# MCU.net
KiCad netlist of a schematic drawn in Altium Designer
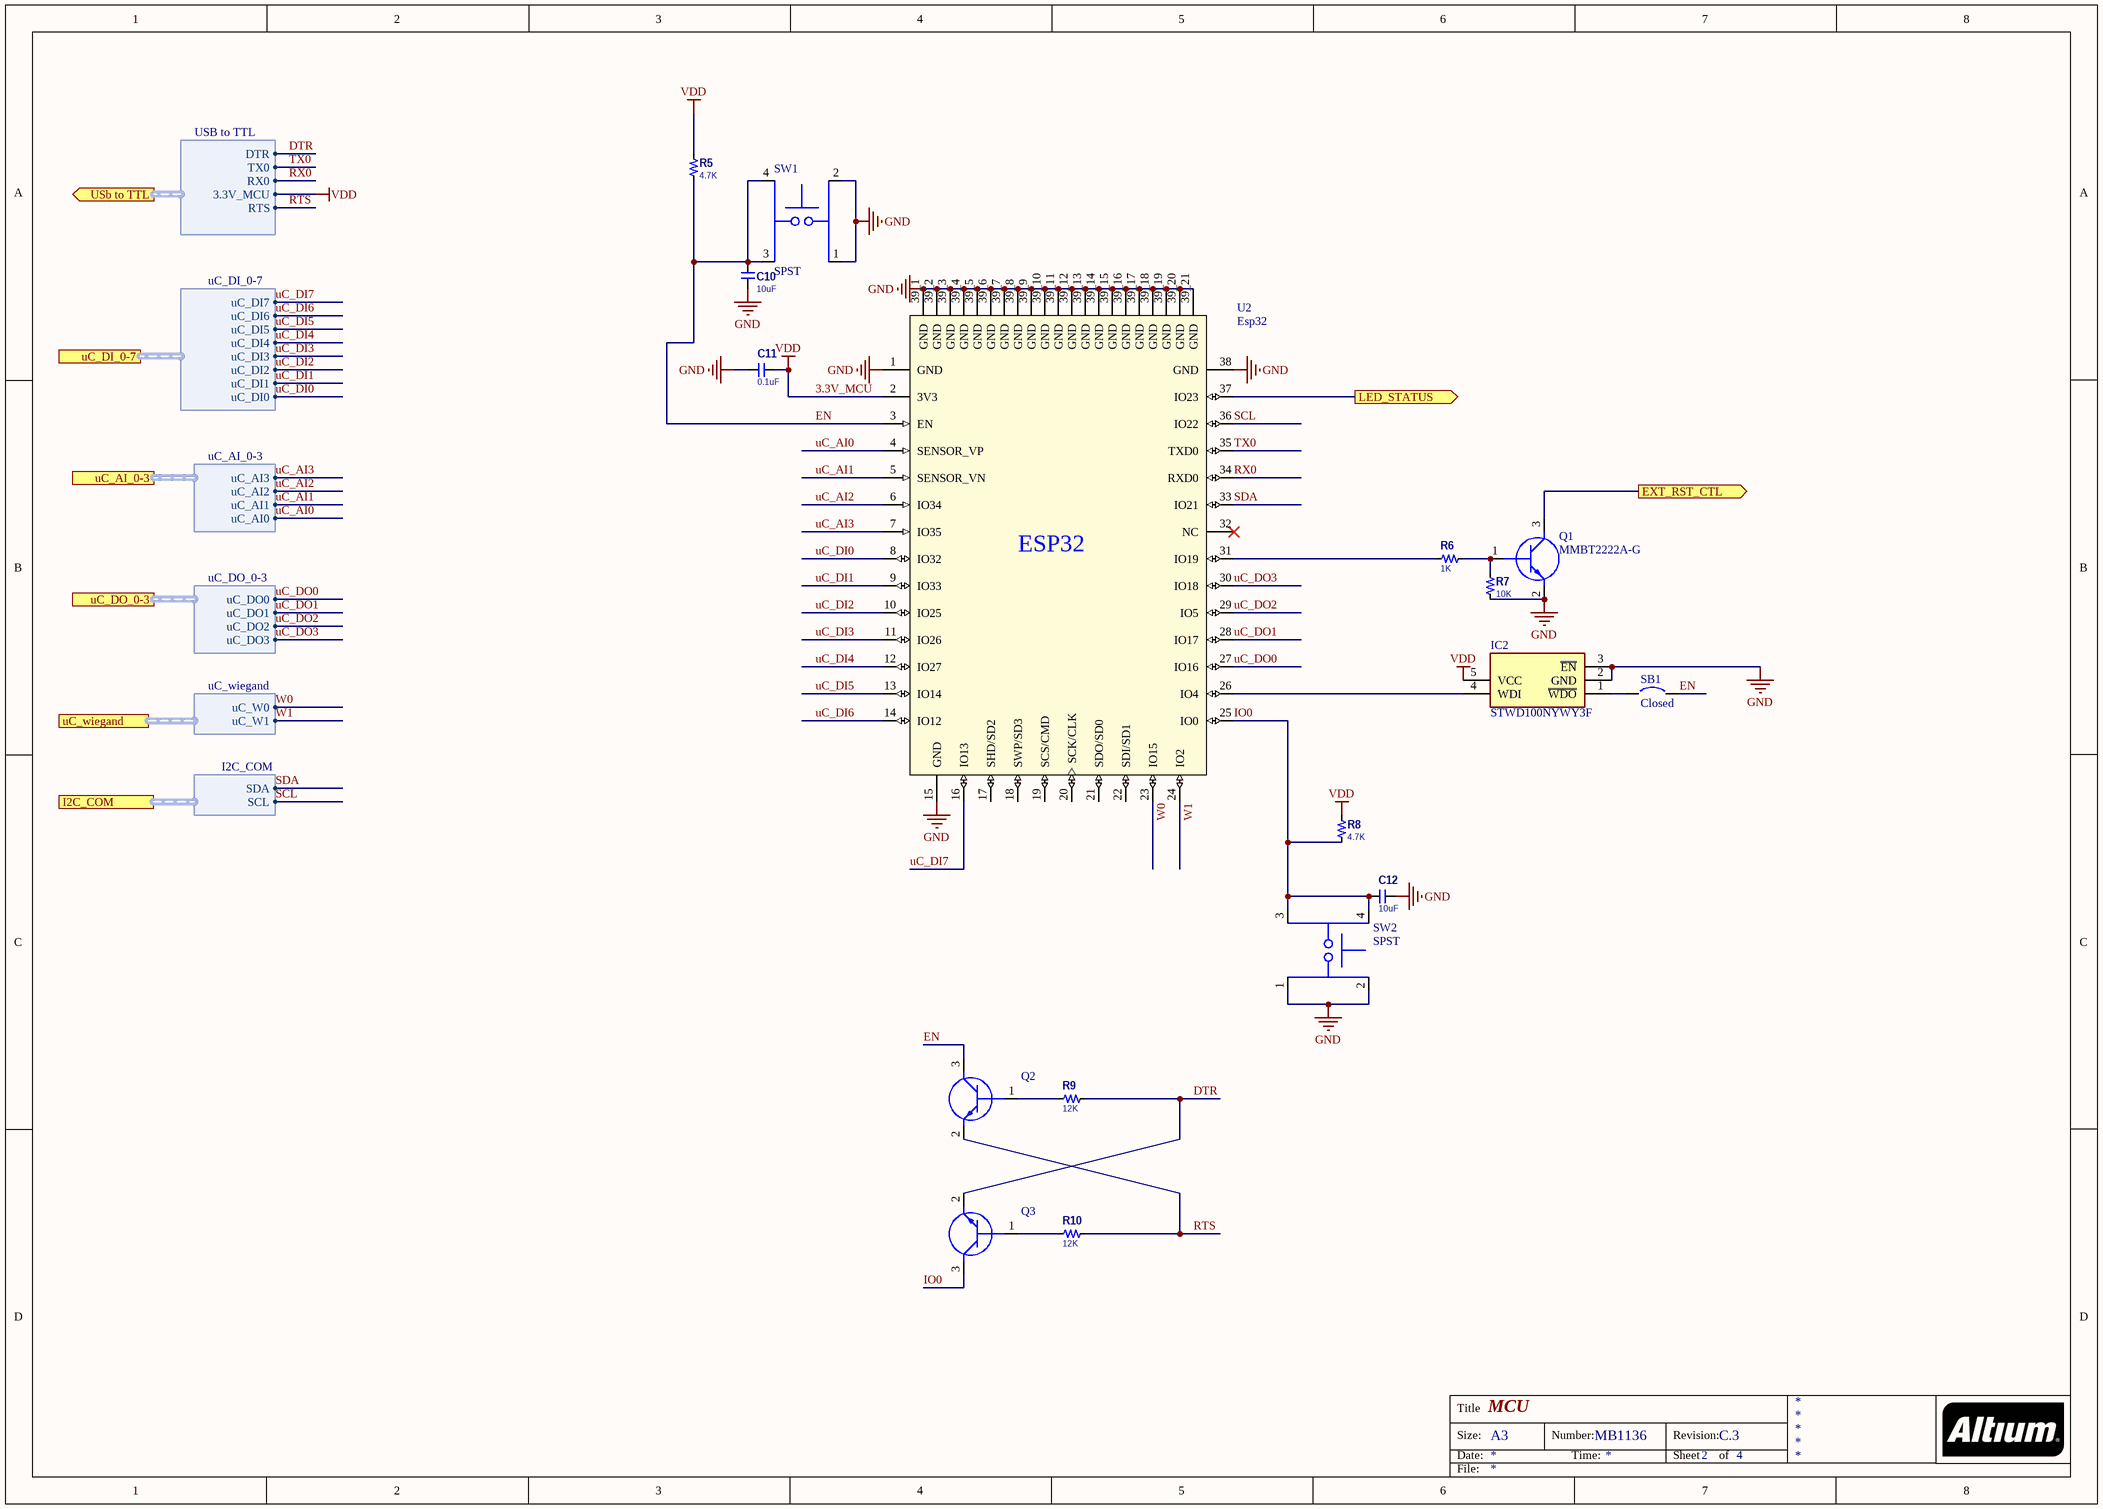
[diagram p0: MCU.SchDoc]

(export (version "E")
  (design (tool "Eeschema 10.0.6"))
  (components
    (comp (ref "C10")
      (value "10uF")
      (footprint "0603-C")
      (description "CAP")
      (fields
        (field (name "MANUFACTURER") "TDK EPCOS")
        (field (name "MANUFACTURER PART NUMBER") "B37941K9105K62")
      )
      (libsource (lib "ESP32_IO_module") (part "CAP"))
    )
    (comp (ref "C11")
      (value "0.1uF")
      (footprint "0603-C")
      (description "CAP")
      (fields
        (field (name "MANUFACTURER") "TDK EPCOS")
        (field (name "MANUFACTURER PART NUMBER") "B37941K9105K62")
      )
      (libsource (lib "ESP32_IO_module") (part "CAP"))
    )
    (comp (ref "C12")
      (value "10uF")
      (footprint "0603-C")
      (description "CAP")
      (fields
        (field (name "MANUFACTURER") "TDK EPCOS")
        (field (name "MANUFACTURER PART NUMBER") "B37941K9105K62")
      )
      (libsource (lib "ESP32_IO_module") (part "CAP"))
    )
    (comp (ref "IC2")
      (value "STWD100NYWY3F")
      (footprint "SamacSys:SOT95P280X145-5N")
      (description "Integrated Circuit")
      (fields (field (name "MOUSER PART NUMBER") "511-STWD100NYWY3F"))
      (libsource (lib "*") (part "STWD100NYWY3F"))
    )
    (comp (ref "Q1")
      (value "MMBT2222A-G")
      (footprint "SamacSys:SOT95P240X115-3N")
      (description "Transistor BJT NPN")
      (fields (field (name "MOUSER PART NUMBER") "750-MMBT2222A-G"))
      (libsource (lib "*") (part "MMBT2222A-G"))
    )
    (comp (ref "Q2")
      (value "MMBT2222A-G")
      (footprint "SOT95P240X115-3N")
      (description "Transistor BJT NPN")
      (fields (field (name "MOUSER PART NUMBER") "750-MMBT2222A-G"))
      (libsource (lib "ESP32_IO_module") (part "MMBT2222A-G_Mirror"))
    )
    (comp (ref "Q3")
      (value "MMBT2222A-G")
      (footprint "SOT95P240X115-3N")
      (description "Transistor BJT NPN")
      (fields (field (name "MOUSER PART NUMBER") "750-MMBT2222A-G"))
      (libsource (lib "ESP32_IO_module") (part "MMBT2222A-G"))
    )
    (comp (ref "R5")
      (value "4.7K")
      (footprint "0603-R")
      (fields
        (field (name "MANUFACTURER") "Panasonic")
        (field (name "MANUFACTURER PART NUMBER") "ERJ-8GEYJ621V")
        (field (name "TOLERANCE") "5%")
      )
      (libsource (lib "ESP32_IO_module") (part "Res_2"))
    )
    (comp (ref "R6")
      (value "1K")
      (footprint "0603-R")
      (fields
        (field (name "MANUFACTURER") "Panasonic")
        (field (name "MANUFACTURER PART NUMBER") "ERJ-8GEYJ621V")
        (field (name "TOLERANCE") "5%")
      )
      (libsource (lib "ESP32_IO_module") (part "Res_2"))
    )
    (comp (ref "R7")
      (value "10K")
      (footprint "0603-R")
      (fields
        (field (name "MANUFACTURER") "Panasonic")
        (field (name "MANUFACTURER PART NUMBER") "ERJ-8GEYJ621V")
        (field (name "TOLERANCE") "5%")
      )
      (libsource (lib "ESP32_IO_module") (part "Res_2"))
    )
    (comp (ref "R8")
      (value "4.7K")
      (footprint "0603-R")
      (fields
        (field (name "MANUFACTURER") "Panasonic")
        (field (name "MANUFACTURER PART NUMBER") "ERJ-8GEYJ621V")
        (field (name "TOLERANCE") "5%")
      )
      (libsource (lib "ESP32_IO_module") (part "Res_2"))
    )
    (comp (ref "R9")
      (value "12K")
      (footprint "0603-R")
      (fields
        (field (name "MANUFACTURER") "Panasonic")
        (field (name "MANUFACTURER PART NUMBER") "ERJ-8GEYJ621V")
        (field (name "TOLERANCE") "5%")
      )
      (libsource (lib "ESP32_IO_module") (part "Res_2"))
    )
    (comp (ref "R10")
      (value "12K")
      (footprint "0603-R")
      (fields
        (field (name "MANUFACTURER") "Panasonic")
        (field (name "MANUFACTURER PART NUMBER") "ERJ-8GEYJ621V")
        (field (name "TOLERANCE") "5%")
      )
      (libsource (lib "ESP32_IO_module") (part "Res_2"))
    )
    (comp (ref "SB1")
      (value "Closed")
      (footprint "SB_0603")
      (description "Circuit Breaker")
      (fields (field (name "PUBLISHER") "Altium Limited"))
      (libsource (lib "IIOT_GATEWAY_MT7621") (part "Circuit Breaker_close"))
    )
    (comp (ref "SW1")
      (value "SPST")
      (footprint "TL3342F160QG")
      (description "E-SWITCH - TL3342F160QG - SWITCH, TACTILE, SPST-NO, 50mA, 12VDC")
      (fields (field (name "MANUFACTURER") "SOFNG") (field (name "MANUFACTURER PART NUMBER") "TS-1187-1816"))
      (libsource (lib "ESP32_IO_module") (part "SWITCH TACTILE SPST-NO 0.05A 12V_EWP"))
    )
    (comp (ref "SW2")
      (value "SPST")
      (footprint "TL3342F160QG")
      (description "E-SWITCH - TL3342F160QG - SWITCH, TACTILE, SPST-NO, 50mA, 12VDC")
      (fields (field (name "MANUFACTURER") "SOFNG") (field (name "MANUFACTURER PART NUMBER") "TS-1187-1816"))
      (libsource (lib "ESP32_IO_module") (part "SWITCH TACTILE SPST-NO 0.05A 12V_EWP"))
    )
    (comp (ref "U2")
      (value "Esp32")
      (footprint "MODULE_ESP32-WROOM-32")
      (description "Bluetooth, WiFi Transceiver Module 2.4GHz ~ 2.5GHz Surface Mount")
      (fields (field (name "MF") "Espressif Systems") (field (name "DIGI-KEY_PART_NUMBER") "1904-1010-1-ND"))
      (libsource (lib "ESP32_IO_module") (part "ESP32-WROOM-32"))
    )
  )
  (nets
    (net (code "9") (name "/DTR") (class "Default")
      (node (ref "Q3") (pin "2") (pinfunction "E_2") (pintype "passive"))
      (node (ref "R9") (pin "1") (pinfunction "1_1") (pintype "passive"))
    )
    (net (code "10") (name "/EN") (class "Default")
      (node (ref "C10") (pin "1") (pinfunction "1_1") (pintype "passive"))
      (node (ref "Q2") (pin "3") (pinfunction "C_3") (pintype "passive"))
      (node (ref "R5") (pin "1") (pinfunction "1_1") (pintype "passive"))
      (node (ref "SB1") (pin "2") (pinfunction "2_2") (pintype "passive"))
      (node (ref "SW1") (pin "3") (pinfunction "3_3") (pintype "passive"))
      (node (ref "SW1") (pin "4") (pinfunction "4_4") (pintype "passive"))
      (node (ref "U2") (pin "3") (pinfunction "EN_3") (pintype "input"))
    )
    (net (code "11") (name "/EXT_RST_CTL") (class "Default")
      (node (ref "Q1") (pin "3") (pinfunction "C_3") (pintype "passive"))
    )
    (net (code "12") (name "/IO0") (class "Default")
      (node (ref "C12") (pin "1") (pinfunction "1_1") (pintype "passive"))
      (node (ref "Q3") (pin "3") (pinfunction "C_3") (pintype "passive"))
      (node (ref "R8") (pin "1") (pinfunction "1_1") (pintype "passive"))
      (node (ref "SW2") (pin "3") (pinfunction "3_3") (pintype "passive"))
      (node (ref "SW2") (pin "4") (pinfunction "4_4") (pintype "passive"))
      (node (ref "U2") (pin "25") (pinfunction "IO0_25") (pintype "bidirectional"))
    )
    (net (code "13") (name "/LED_STATUS") (class "Default")
      (node (ref "U2") (pin "37") (pinfunction "IO23_37") (pintype "bidirectional"))
    )
    (net (code "14") (name "/RTS") (class "Default")
      (node (ref "Q2") (pin "2") (pinfunction "E_2") (pintype "passive"))
      (node (ref "R10") (pin "1") (pinfunction "1_1") (pintype "passive"))
    )
    (net (code "15") (name "/RX0") (class "Default")
      (node (ref "U2") (pin "34") (pinfunction "RXD0_34") (pintype "bidirectional"))
    )
    (net (code "16") (name "/SCL") (class "Default")
      (node (ref "U2") (pin "36") (pinfunction "IO22_36") (pintype "bidirectional"))
    )
    (net (code "17") (name "/SDA") (class "Default")
      (node (ref "U2") (pin "33") (pinfunction "IO21_33") (pintype "bidirectional"))
    )
    (net (code "18") (name "/TX0") (class "Default")
      (node (ref "U2") (pin "35") (pinfunction "TXD0_35") (pintype "bidirectional"))
    )
    (net (code "19") (name "/W0") (class "Default")
      (node (ref "U2") (pin "23") (pinfunction "IO15_23") (pintype "bidirectional"))
    )
    (net (code "20") (name "/W1") (class "Default")
      (node (ref "U2") (pin "24") (pinfunction "IO2_24") (pintype "bidirectional"))
    )
    (net (code "21") (name "/uC_AI0") (class "Default")
      (node (ref "U2") (pin "4") (pinfunction "SENSOR_VP_4") (pintype "input"))
    )
    (net (code "22") (name "/uC_AI1") (class "Default")
      (node (ref "U2") (pin "5") (pinfunction "SENSOR_VN_5") (pintype "input"))
    )
    (net (code "23") (name "/uC_AI2") (class "Default")
      (node (ref "U2") (pin "6") (pinfunction "IO34_6") (pintype "input"))
    )
    (net (code "24") (name "/uC_AI3") (class "Default")
      (node (ref "U2") (pin "7") (pinfunction "IO35_7") (pintype "input"))
    )
    (net (code "25") (name "/uC_DI0") (class "Default")
      (node (ref "U2") (pin "8") (pinfunction "IO32_8") (pintype "bidirectional"))
    )
    (net (code "26") (name "/uC_DI1") (class "Default")
      (node (ref "U2") (pin "9") (pinfunction "IO33_9") (pintype "bidirectional"))
    )
    (net (code "27") (name "/uC_DI2") (class "Default")
      (node (ref "U2") (pin "10") (pinfunction "IO25_10") (pintype "bidirectional"))
    )
    (net (code "28") (name "/uC_DI3") (class "Default")
      (node (ref "U2") (pin "11") (pinfunction "IO26_11") (pintype "bidirectional"))
    )
    (net (code "29") (name "/uC_DI4") (class "Default")
      (node (ref "U2") (pin "12") (pinfunction "IO27_12") (pintype "bidirectional"))
    )
    (net (code "30") (name "/uC_DI5") (class "Default")
      (node (ref "U2") (pin "13") (pinfunction "IO14_13") (pintype "bidirectional"))
    )
    (net (code "31") (name "/uC_DI6") (class "Default")
      (node (ref "U2") (pin "14") (pinfunction "IO12_14") (pintype "bidirectional"))
    )
    (net (code "32") (name "/uC_DI7") (class "Default")
      (node (ref "U2") (pin "16") (pinfunction "IO13_16") (pintype "bidirectional"))
    )
    (net (code "33") (name "/uC_DO0") (class "Default")
      (node (ref "U2") (pin "27") (pinfunction "IO16_27") (pintype "bidirectional"))
    )
    (net (code "34") (name "/uC_DO1") (class "Default")
      (node (ref "U2") (pin "28") (pinfunction "IO17_28") (pintype "bidirectional"))
    )
    (net (code "35") (name "/uC_DO2") (class "Default")
      (node (ref "U2") (pin "29") (pinfunction "IO5_29") (pintype "bidirectional"))
    )
    (net (code "36") (name "/uC_DO3") (class "Default")
      (node (ref "U2") (pin "30") (pinfunction "IO18_30") (pintype "bidirectional"))
    )
    (net (code "43") (name "GND") (class "Default")
      (node (ref "C10") (pin "2") (pinfunction "2_2") (pintype "passive"))
      (node (ref "C11") (pin "1") (pinfunction "1_1") (pintype "passive"))
      (node (ref "C12") (pin "2") (pinfunction "2_2") (pintype "passive"))
      (node (ref "IC2") (pin "2") (pinfunction "GND_2") (pintype "passive"))
      (node (ref "IC2") (pin "3") (pinfunction "~{EN}_3") (pintype "passive"))
      (node (ref "Q1") (pin "2") (pinfunction "E_2") (pintype "passive"))
      (node (ref "R7") (pin "1") (pinfunction "1_1") (pintype "passive"))
      (node (ref "SW1") (pin "1") (pinfunction "1_1") (pintype "passive"))
      (node (ref "SW1") (pin "2") (pinfunction "2_2") (pintype "passive"))
      (node (ref "SW2") (pin "1") (pinfunction "1_1") (pintype "passive"))
      (node (ref "SW2") (pin "2") (pinfunction "2_2") (pintype "passive"))
      (node (ref "U2") (pin "1") (pinfunction "GND_1") (pintype "power_in"))
      (node (ref "U2") (pin "15") (pinfunction "GND_15") (pintype "power_in"))
      (node (ref "U2") (pin "38") (pinfunction "GND_38") (pintype "power_in"))
      (node (ref "U2") (pin "39_1") (pinfunction "GND_39_1") (pintype "power_in"))
      (node (ref "U2") (pin "39_10") (pinfunction "GND_39_10") (pintype "power_in"))
      (node (ref "U2") (pin "39_11") (pinfunction "GND_39_11") (pintype "power_in"))
      (node (ref "U2") (pin "39_12") (pinfunction "GND_39_12") (pintype "power_in"))
      (node (ref "U2") (pin "39_13") (pinfunction "GND_39_13") (pintype "power_in"))
      (node (ref "U2") (pin "39_14") (pinfunction "GND_39_14") (pintype "power_in"))
      (node (ref "U2") (pin "39_15") (pinfunction "GND_39_15") (pintype "power_in"))
      (node (ref "U2") (pin "39_16") (pinfunction "GND_39_16") (pintype "power_in"))
      (node (ref "U2") (pin "39_17") (pinfunction "GND_39_17") (pintype "power_in"))
      (node (ref "U2") (pin "39_18") (pinfunction "GND_39_18") (pintype "power_in"))
      (node (ref "U2") (pin "39_19") (pinfunction "GND_39_19") (pintype "power_in"))
      (node (ref "U2") (pin "39_2") (pinfunction "GND_39_2") (pintype "power_in"))
      (node (ref "U2") (pin "39_20") (pinfunction "GND_39_20") (pintype "power_in"))
      (node (ref "U2") (pin "39_21") (pinfunction "GND_39_21") (pintype "power_in"))
      (node (ref "U2") (pin "39_3") (pinfunction "GND_39_3") (pintype "power_in"))
      (node (ref "U2") (pin "39_4") (pinfunction "GND_39_4") (pintype "power_in"))
      (node (ref "U2") (pin "39_5") (pinfunction "GND_39_5") (pintype "power_in"))
      (node (ref "U2") (pin "39_6") (pinfunction "GND_39_6") (pintype "power_in"))
      (node (ref "U2") (pin "39_7") (pinfunction "GND_39_7") (pintype "power_in"))
      (node (ref "U2") (pin "39_8") (pinfunction "GND_39_8") (pintype "power_in"))
      (node (ref "U2") (pin "39_9") (pinfunction "GND_39_9") (pintype "power_in"))
    )
    (net (code "44") (name "Net-(IC2-WDI)") (class "Default")
      (node (ref "IC2") (pin "4") (pinfunction "WDI_4") (pintype "passive"))
      (node (ref "U2") (pin "26") (pinfunction "IO4_26") (pintype "bidirectional"))
    )
    (net (code "45") (name "Net-(IC2-~{WDO})") (class "Default")
      (node (ref "IC2") (pin "1") (pinfunction "~{WDO}_1") (pintype "passive"))
      (node (ref "SB1") (pin "1") (pinfunction "1_1") (pintype "passive"))
    )
    (net (code "46") (name "Net-(Q1-B)") (class "Default")
      (node (ref "Q1") (pin "1") (pinfunction "B_1") (pintype "passive"))
      (node (ref "R6") (pin "1") (pinfunction "1_1") (pintype "passive"))
      (node (ref "R7") (pin "2") (pinfunction "2_2") (pintype "passive"))
    )
    (net (code "47") (name "Net-(Q2-B)") (class "Default")
      (node (ref "Q2") (pin "1") (pinfunction "B_1") (pintype "passive"))
      (node (ref "R9") (pin "2") (pinfunction "2_2") (pintype "passive"))
    )
    (net (code "48") (name "Net-(Q3-B)") (class "Default")
      (node (ref "Q3") (pin "1") (pinfunction "B_1") (pintype "passive"))
      (node (ref "R10") (pin "2") (pinfunction "2_2") (pintype "passive"))
    )
    (net (code "49") (name "Net-(U2-IO19)") (class "Default")
      (node (ref "R6") (pin "2") (pinfunction "2_2") (pintype "passive"))
      (node (ref "U2") (pin "31") (pinfunction "IO19_31") (pintype "bidirectional"))
    )
    (net (code "50") (name "VDD") (class "Default")
      (node (ref "C11") (pin "2") (pinfunction "2_2") (pintype "passive"))
      (node (ref "IC2") (pin "5") (pinfunction "VCC_5") (pintype "passive"))
      (node (ref "R5") (pin "2") (pinfunction "2_2") (pintype "passive"))
      (node (ref "R8") (pin "2") (pinfunction "2_2") (pintype "passive"))
      (node (ref "U2") (pin "2") (pinfunction "3V3_2") (pintype "power_in"))
    )
    (net (code "51") (name "unconnected-(U2-NC-Pad32)") (class "Default")
      (node (ref "U2") (pin "32") (pinfunction "NC_32") (pintype "passive+no_connect"))
    )
    (net (code "52") (name "unconnected-(U2-SCK{slash}CLK-Pad20)") (class "Default")
      (node (ref "U2") (pin "20") (pinfunction "SCK/CLK_20") (pintype "bidirectional"))
    )
    (net (code "53") (name "unconnected-(U2-SCS{slash}CMD-Pad19)") (class "Default")
      (node (ref "U2") (pin "19") (pinfunction "SCS/CMD_19") (pintype "bidirectional"))
    )
    (net (code "54") (name "unconnected-(U2-SDI{slash}SD1-Pad22)") (class "Default")
      (node (ref "U2") (pin "22") (pinfunction "SDI/SD1_22") (pintype "bidirectional"))
    )
    (net (code "55") (name "unconnected-(U2-SDO{slash}SD0-Pad21)") (class "Default")
      (node (ref "U2") (pin "21") (pinfunction "SDO/SD0_21") (pintype "bidirectional"))
    )
    (net (code "56") (name "unconnected-(U2-SHD{slash}SD2-Pad17)") (class "Default")
      (node (ref "U2") (pin "17") (pinfunction "SHD/SD2_17") (pintype "bidirectional"))
    )
    (net (code "57") (name "unconnected-(U2-SWP{slash}SD3-Pad18)") (class "Default")
      (node (ref "U2") (pin "18") (pinfunction "SWP/SD3_18") (pintype "bidirectional"))
    )
  )
)
